# Power.net
KiCad netlist of a schematic drawn in Altium Designer
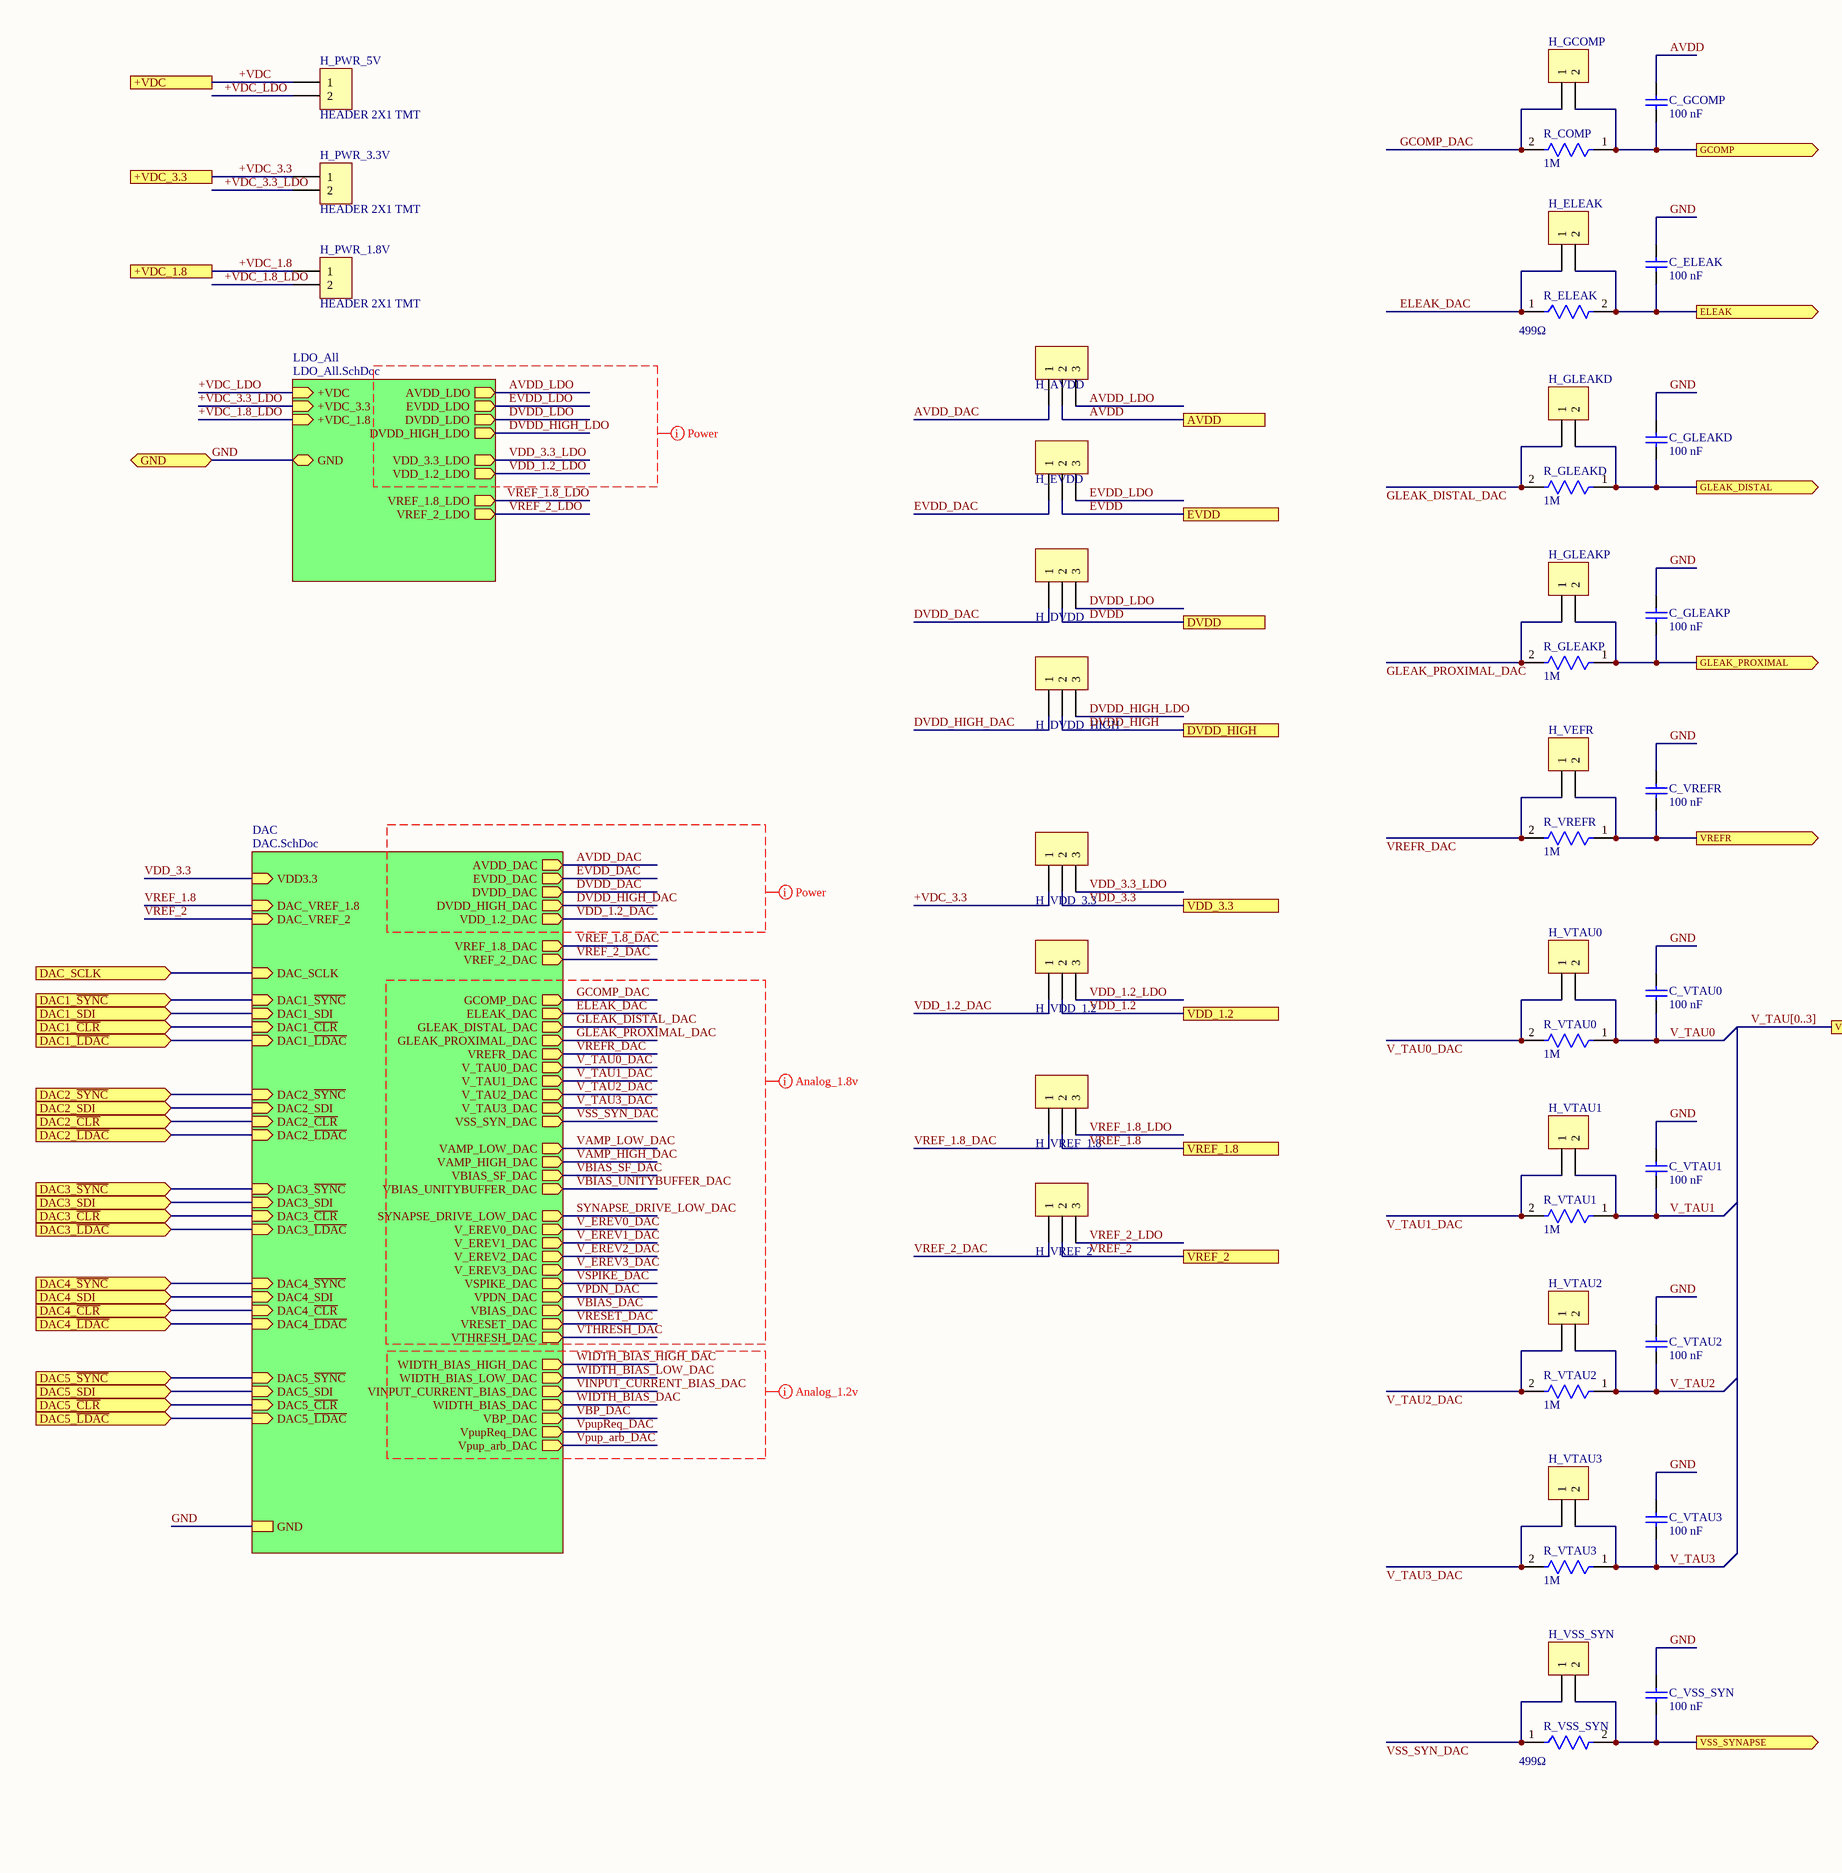
[diagram p0: Power.SchDoc, left]
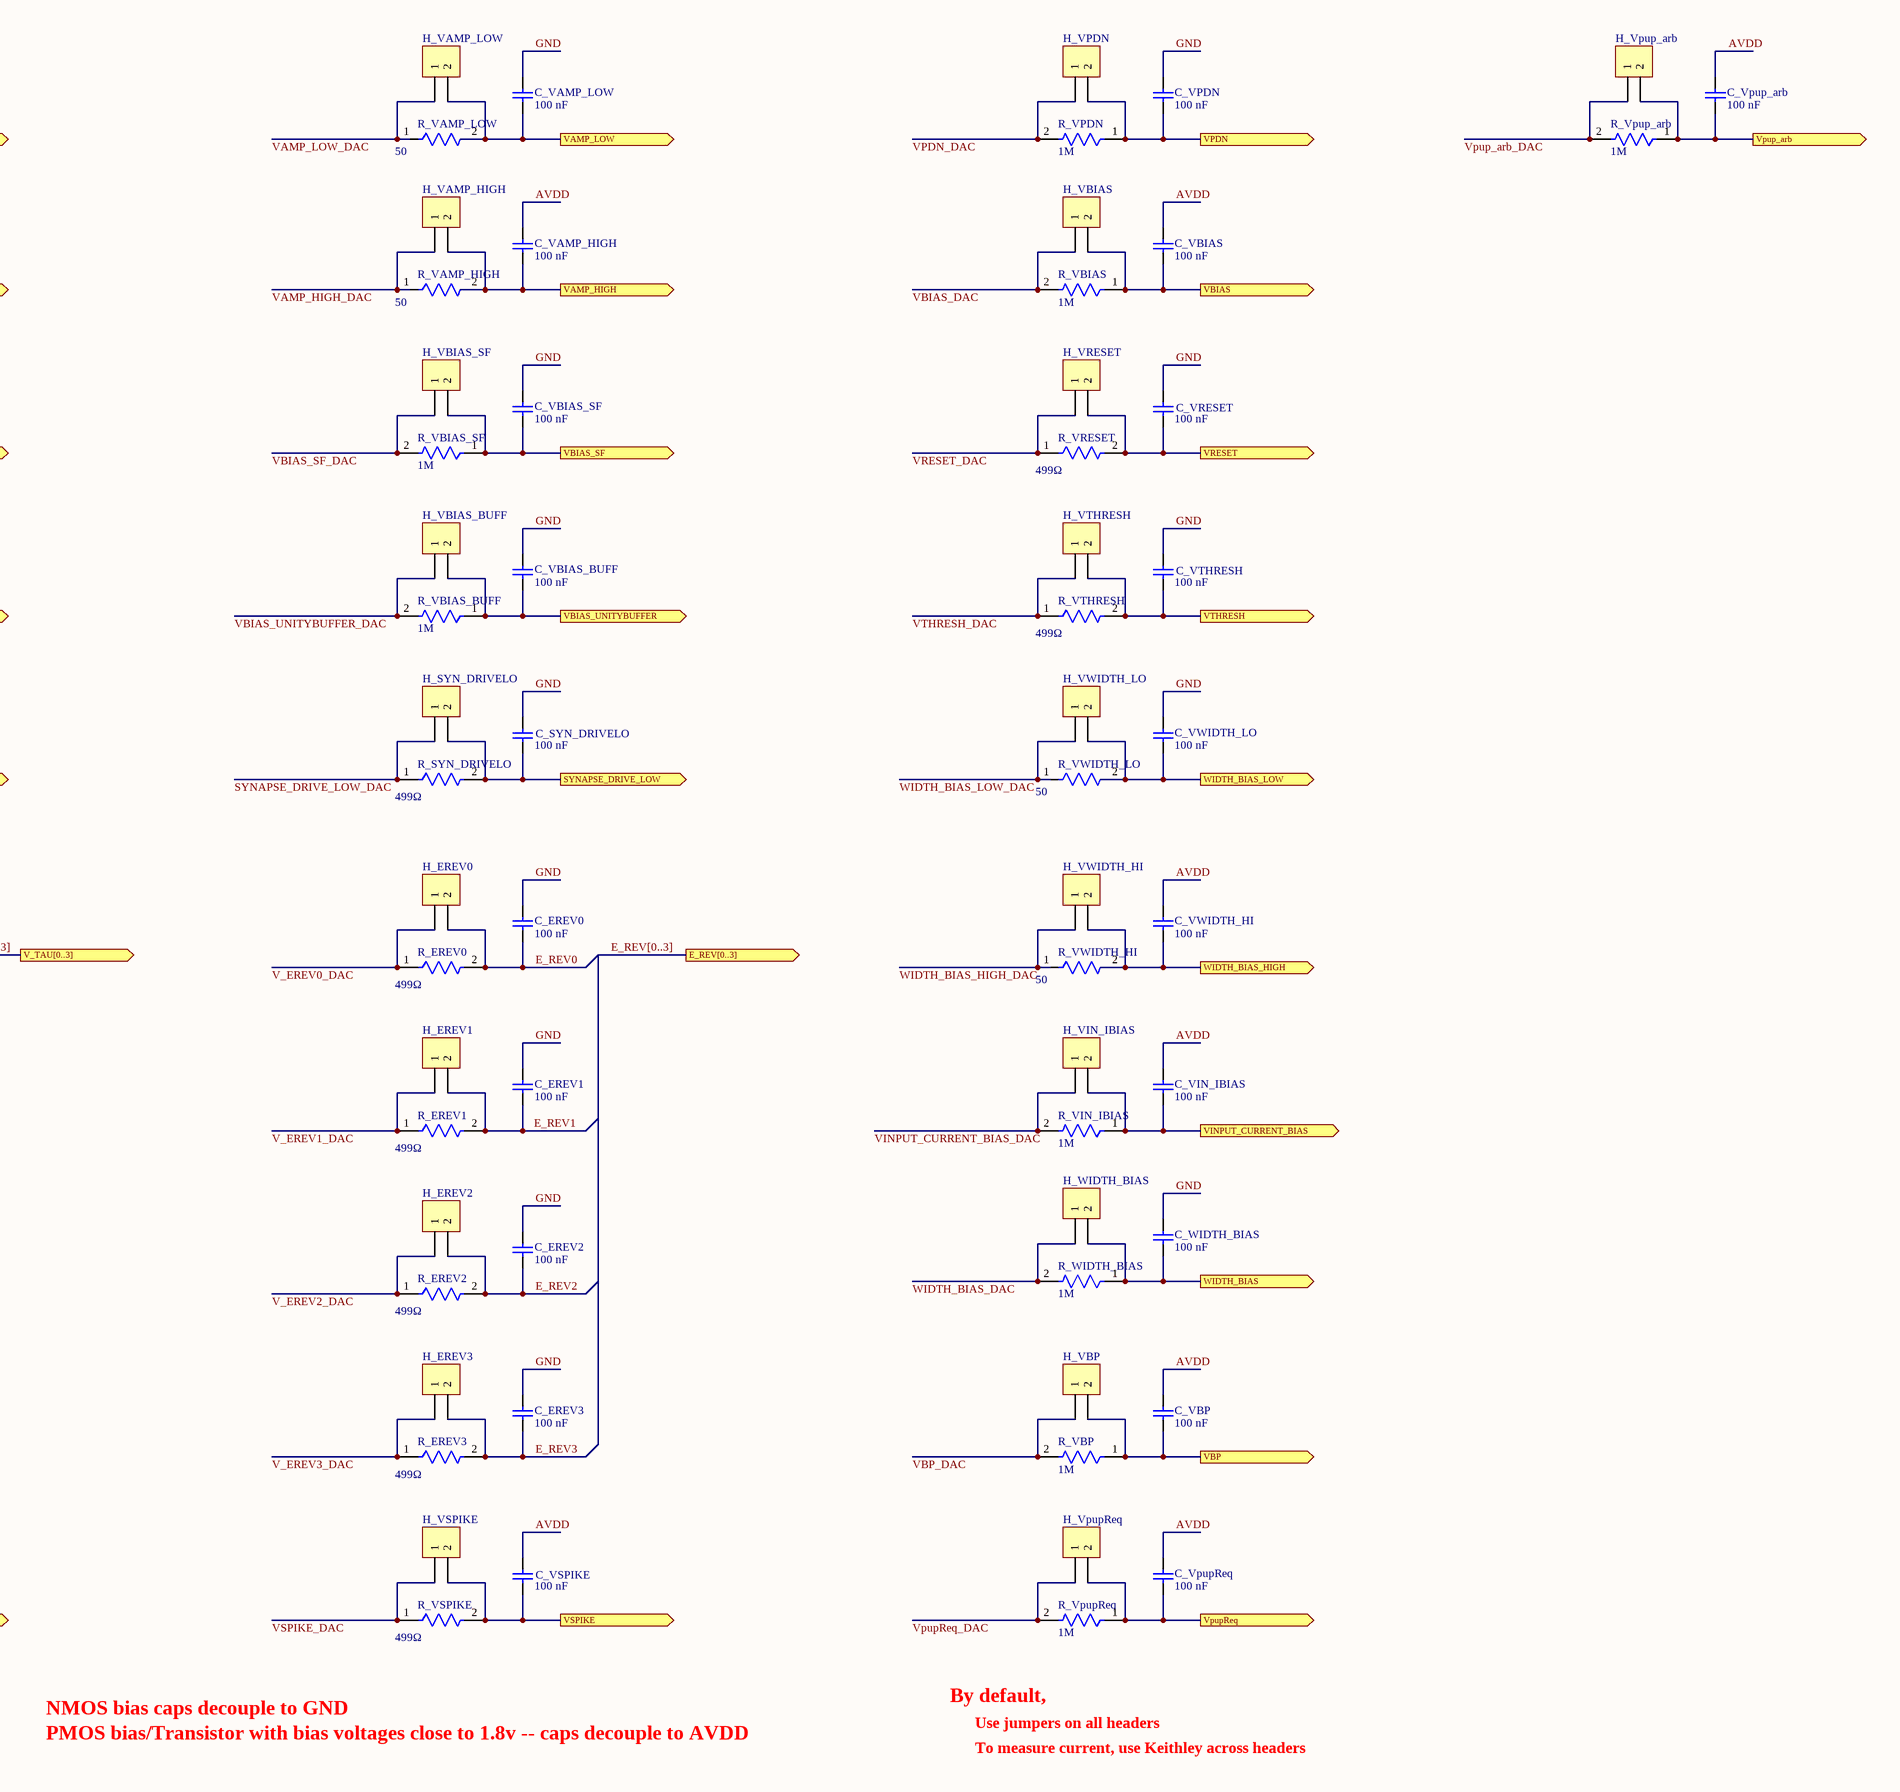
[diagram p1: Power.SchDoc, right]

(export (version "E")
  (design (tool "Eeschema 10.0.6"))
  (components
    (comp (ref "C_ELEAK")
      (value "100 nF")
      (footprint "KEMET C0805C104J8RACTU")
      (description "CAP CER 0.1UF 10V X7R 0805\r\n±10% 10V Ceramic Capacitor X7R 0805 (2012 Metric)")
      (fields (field (name "Comment") "Cap 100nF 0805"))
      (libsource (lib "MRI_ADC") (part "Cap 100nF 0805"))
    )
    (comp (ref "C_EREV0")
      (value "100 nF")
      (footprint "KEMET C0805C104J8RACTU")
      (description "CAP CER 0.1UF 10V X7R 0805\r\n±10% 10V Ceramic Capacitor X7R 0805 (2012 Metric)")
      (fields (field (name "Comment") "Cap 100nF 0805"))
      (libsource (lib "MRI_ADC") (part "Cap 100nF 0805"))
    )
    (comp (ref "C_EREV1")
      (value "100 nF")
      (footprint "KEMET C0805C104J8RACTU")
      (description "CAP CER 0.1UF 10V X7R 0805\r\n±10% 10V Ceramic Capacitor X7R 0805 (2012 Metric)")
      (fields (field (name "Comment") "Cap 100nF 0805"))
      (libsource (lib "MRI_ADC") (part "Cap 100nF 0805"))
    )
    (comp (ref "C_EREV2")
      (value "100 nF")
      (footprint "KEMET C0805C104J8RACTU")
      (description "CAP CER 0.1UF 10V X7R 0805\r\n±10% 10V Ceramic Capacitor X7R 0805 (2012 Metric)")
      (fields (field (name "Comment") "Cap 100nF 0805"))
      (libsource (lib "MRI_ADC") (part "Cap 100nF 0805"))
    )
    (comp (ref "C_EREV3")
      (value "100 nF")
      (footprint "KEMET C0805C104J8RACTU")
      (description "CAP CER 0.1UF 10V X7R 0805\r\n±10% 10V Ceramic Capacitor X7R 0805 (2012 Metric)")
      (fields (field (name "Comment") "Cap 100nF 0805"))
      (libsource (lib "MRI_ADC") (part "Cap 100nF 0805"))
    )
    (comp (ref "C_GCOMP")
      (value "100 nF")
      (footprint "KEMET C0805C104J8RACTU")
      (description "CAP CER 0.1UF 10V X7R 0805\r\n±10% 10V Ceramic Capacitor X7R 0805 (2012 Metric)")
      (fields (field (name "Comment") "Cap 100nF 0805"))
      (libsource (lib "MRI_ADC") (part "Cap 100nF 0805"))
    )
    (comp (ref "C_GLEAKD")
      (value "100 nF")
      (footprint "KEMET C0805C104J8RACTU")
      (description "CAP CER 0.1UF 10V X7R 0805\r\n±10% 10V Ceramic Capacitor X7R 0805 (2012 Metric)")
      (fields (field (name "Comment") "Cap 100nF 0805"))
      (libsource (lib "MRI_ADC") (part "Cap 100nF 0805"))
    )
    (comp (ref "C_GLEAKP")
      (value "100 nF")
      (footprint "KEMET C0805C104J8RACTU")
      (description "CAP CER 0.1UF 10V X7R 0805\r\n±10% 10V Ceramic Capacitor X7R 0805 (2012 Metric)")
      (fields (field (name "Comment") "Cap 100nF 0805"))
      (libsource (lib "MRI_ADC") (part "Cap 100nF 0805"))
    )
    (comp (ref "C_SYN_DRIVELO")
      (value "100 nF")
      (footprint "KEMET C0805C104J8RACTU")
      (description "CAP CER 0.1UF 10V X7R 0805\r\n±10% 10V Ceramic Capacitor X7R 0805 (2012 Metric)")
      (fields (field (name "Comment") "Cap 100nF 0805"))
      (libsource (lib "MRI_ADC") (part "Cap 100nF 0805"))
    )
    (comp (ref "C_VAMP_HIGH")
      (value "100 nF")
      (footprint "KEMET C0805C104J8RACTU")
      (description "CAP CER 0.1UF 10V X7R 0805\r\n±10% 10V Ceramic Capacitor X7R 0805 (2012 Metric)")
      (fields (field (name "Comment") "Cap 100nF 0805"))
      (libsource (lib "MRI_ADC") (part "Cap 100nF 0805"))
    )
    (comp (ref "C_VAMP_LOW")
      (value "100 nF")
      (footprint "KEMET C0805C104J8RACTU")
      (description "CAP CER 0.1UF 10V X7R 0805\r\n±10% 10V Ceramic Capacitor X7R 0805 (2012 Metric)")
      (fields (field (name "Comment") "Cap 100nF 0805"))
      (libsource (lib "MRI_ADC") (part "Cap 100nF 0805"))
    )
    (comp (ref "C_VBIAS")
      (value "100 nF")
      (footprint "KEMET C0805C104J8RACTU")
      (description "CAP CER 0.1UF 10V X7R 0805\r\n±10% 10V Ceramic Capacitor X7R 0805 (2012 Metric)")
      (fields (field (name "Comment") "Cap 100nF 0805"))
      (libsource (lib "MRI_ADC") (part "Cap 100nF 0805"))
    )
    (comp (ref "C_VBIAS_BUFF")
      (value "100 nF")
      (footprint "KEMET C0805C104J8RACTU")
      (description "CAP CER 0.1UF 10V X7R 0805\r\n±10% 10V Ceramic Capacitor X7R 0805 (2012 Metric)")
      (fields (field (name "Comment") "Cap 100nF 0805"))
      (libsource (lib "MRI_ADC") (part "Cap 100nF 0805"))
    )
    (comp (ref "C_VBIAS_SF")
      (value "100 nF")
      (footprint "KEMET C0805C104J8RACTU")
      (description "CAP CER 0.1UF 10V X7R 0805\r\n±10% 10V Ceramic Capacitor X7R 0805 (2012 Metric)")
      (fields (field (name "Comment") "Cap 100nF 0805"))
      (libsource (lib "MRI_ADC") (part "Cap 100nF 0805"))
    )
    (comp (ref "C_VBP")
      (value "100 nF")
      (footprint "KEMET C0805C104J8RACTU")
      (description "CAP CER 0.1UF 10V X7R 0805\r\n±10% 10V Ceramic Capacitor X7R 0805 (2012 Metric)")
      (fields (field (name "Comment") "Cap 100nF 0805"))
      (libsource (lib "MRI_ADC") (part "Cap 100nF 0805"))
    )
    (comp (ref "C_VIN_IBIAS")
      (value "100 nF")
      (footprint "KEMET C0805C104J8RACTU")
      (description "CAP CER 0.1UF 10V X7R 0805\r\n±10% 10V Ceramic Capacitor X7R 0805 (2012 Metric)")
      (fields (field (name "Comment") "Cap 100nF 0805"))
      (libsource (lib "MRI_ADC") (part "Cap 100nF 0805"))
    )
    (comp (ref "C_VPDN")
      (value "100 nF")
      (footprint "KEMET C0805C104J8RACTU")
      (description "CAP CER 0.1UF 10V X7R 0805\r\n±10% 10V Ceramic Capacitor X7R 0805 (2012 Metric)")
      (fields (field (name "Comment") "Cap 100nF 0805"))
      (libsource (lib "MRI_ADC") (part "Cap 100nF 0805"))
    )
    (comp (ref "C_VpupReq")
      (value "100 nF")
      (footprint "KEMET C0805C104J8RACTU")
      (description "CAP CER 0.1UF 10V X7R 0805\r\n±10% 10V Ceramic Capacitor X7R 0805 (2012 Metric)")
      (fields (field (name "Comment") "Cap 100nF 0805"))
      (libsource (lib "MRI_ADC") (part "Cap 100nF 0805"))
    )
    (comp (ref "C_Vpup_arb")
      (value "100 nF")
      (footprint "KEMET C0805C104J8RACTU")
      (description "CAP CER 0.1UF 10V X7R 0805\r\n±10% 10V Ceramic Capacitor X7R 0805 (2012 Metric)")
      (fields (field (name "Comment") "Cap 100nF 0805"))
      (libsource (lib "MRI_ADC") (part "Cap 100nF 0805"))
    )
    (comp (ref "C_VREFR")
      (value "100 nF")
      (footprint "KEMET C0805C104J8RACTU")
      (description "CAP CER 0.1UF 10V X7R 0805\r\n±10% 10V Ceramic Capacitor X7R 0805 (2012 Metric)")
      (fields (field (name "Comment") "Cap 100nF 0805"))
      (libsource (lib "MRI_ADC") (part "Cap 100nF 0805"))
    )
    (comp (ref "C_VRESET")
      (value "100 nF")
      (footprint "KEMET C0805C104J8RACTU")
      (description "CAP CER 0.1UF 10V X7R 0805\r\n±10% 10V Ceramic Capacitor X7R 0805 (2012 Metric)")
      (fields (field (name "Comment") "Cap 100nF 0805"))
      (libsource (lib "MRI_ADC") (part "Cap 100nF 0805"))
    )
    (comp (ref "C_VSPIKE")
      (value "100 nF")
      (footprint "KEMET C0805C104J8RACTU")
      (description "CAP CER 0.1UF 10V X7R 0805\r\n±10% 10V Ceramic Capacitor X7R 0805 (2012 Metric)")
      (fields (field (name "Comment") "Cap 100nF 0805"))
      (libsource (lib "MRI_ADC") (part "Cap 100nF 0805"))
    )
    (comp (ref "C_VSS_SYN")
      (value "100 nF")
      (footprint "KEMET C0805C104J8RACTU")
      (description "CAP CER 0.1UF 10V X7R 0805\r\n±10% 10V Ceramic Capacitor X7R 0805 (2012 Metric)")
      (fields (field (name "Comment") "Cap 100nF 0805"))
      (libsource (lib "MRI_ADC") (part "Cap 100nF 0805"))
    )
    (comp (ref "C_VTAU0")
      (value "100 nF")
      (footprint "KEMET C0805C104J8RACTU")
      (description "CAP CER 0.1UF 10V X7R 0805\r\n±10% 10V Ceramic Capacitor X7R 0805 (2012 Metric)")
      (fields (field (name "Comment") "Cap 100nF 0805"))
      (libsource (lib "MRI_ADC") (part "Cap 100nF 0805"))
    )
    (comp (ref "C_VTAU1")
      (value "100 nF")
      (footprint "KEMET C0805C104J8RACTU")
      (description "CAP CER 0.1UF 10V X7R 0805\r\n±10% 10V Ceramic Capacitor X7R 0805 (2012 Metric)")
      (fields (field (name "Comment") "Cap 100nF 0805"))
      (libsource (lib "MRI_ADC") (part "Cap 100nF 0805"))
    )
    (comp (ref "C_VTAU2")
      (value "100 nF")
      (footprint "KEMET C0805C104J8RACTU")
      (description "CAP CER 0.1UF 10V X7R 0805\r\n±10% 10V Ceramic Capacitor X7R 0805 (2012 Metric)")
      (fields (field (name "Comment") "Cap 100nF 0805"))
      (libsource (lib "MRI_ADC") (part "Cap 100nF 0805"))
    )
    (comp (ref "C_VTAU3")
      (value "100 nF")
      (footprint "KEMET C0805C104J8RACTU")
      (description "CAP CER 0.1UF 10V X7R 0805\r\n±10% 10V Ceramic Capacitor X7R 0805 (2012 Metric)")
      (fields (field (name "Comment") "Cap 100nF 0805"))
      (libsource (lib "MRI_ADC") (part "Cap 100nF 0805"))
    )
    (comp (ref "C_VTHRESH")
      (value "100 nF")
      (footprint "KEMET C0805C104J8RACTU")
      (description "CAP CER 0.1UF 10V X7R 0805\r\n±10% 10V Ceramic Capacitor X7R 0805 (2012 Metric)")
      (fields (field (name "Comment") "Cap 100nF 0805"))
      (libsource (lib "MRI_ADC") (part "Cap 100nF 0805"))
    )
    (comp (ref "C_VWIDTH_HI")
      (value "100 nF")
      (footprint "KEMET C0805C104J8RACTU")
      (description "CAP CER 0.1UF 10V X7R 0805\r\n±10% 10V Ceramic Capacitor X7R 0805 (2012 Metric)")
      (fields (field (name "Comment") "Cap 100nF 0805"))
      (libsource (lib "MRI_ADC") (part "Cap 100nF 0805"))
    )
    (comp (ref "C_VWIDTH_LO")
      (value "100 nF")
      (footprint "KEMET C0805C104J8RACTU")
      (description "CAP CER 0.1UF 10V X7R 0805\r\n±10% 10V Ceramic Capacitor X7R 0805 (2012 Metric)")
      (fields (field (name "Comment") "Cap 100nF 0805"))
      (libsource (lib "MRI_ADC") (part "Cap 100nF 0805"))
    )
    (comp (ref "C_WIDTH_BIAS")
      (value "100 nF")
      (footprint "KEMET C0805C104J8RACTU")
      (description "CAP CER 0.1UF 10V X7R 0805\r\n±10% 10V Ceramic Capacitor X7R 0805 (2012 Metric)")
      (fields (field (name "Comment") "Cap 100nF 0805"))
      (libsource (lib "MRI_ADC") (part "Cap 100nF 0805"))
    )
    (comp (ref "H_AVDD")
      (value "HEADER 3X1 TMT")
      (footprint "Samtec TSW-103-07-L-S")
      (description "CONN HEADER VERT 3POS 2.54MM\r\nConnector Header Through Hole 3 position 0.100\" (2.54mm)")
      (libsource (lib "MRI_ADC") (part "HEADER 3X1 TMT"))
    )
    (comp (ref "H_DVDD")
      (value "HEADER 3X1 TMT")
      (footprint "Samtec TSW-103-07-L-S")
      (description "CONN HEADER VERT 3POS 2.54MM\r\nConnector Header Through Hole 3 position 0.100\" (2.54mm)")
      (libsource (lib "MRI_ADC") (part "HEADER 3X1 TMT"))
    )
    (comp (ref "H_DVDD_HIGH")
      (value "HEADER 3X1 TMT")
      (footprint "Samtec TSW-103-07-L-S")
      (description "CONN HEADER VERT 3POS 2.54MM\r\nConnector Header Through Hole 3 position 0.100\" (2.54mm)")
      (libsource (lib "MRI_ADC") (part "HEADER 3X1 TMT"))
    )
    (comp (ref "H_ELEAK")
      (value "HEADER 2X1 TMT")
      (footprint "Samtec TSW-102-07-G-S")
      (description "CONN HEADER VERT 2POS 2.54MM\r\nConnector Header Through Hole 2 position 0.100\" (2.54mm)")
      (libsource (lib "MRI_ADC") (part "HEADER 2X1 TMT"))
    )
    (comp (ref "H_EREV0")
      (value "HEADER 2X1 TMT")
      (footprint "Samtec TSW-102-07-G-S")
      (description "CONN HEADER VERT 2POS 2.54MM\r\nConnector Header Through Hole 2 position 0.100\" (2.54mm)")
      (libsource (lib "MRI_ADC") (part "HEADER 2X1 TMT"))
    )
    (comp (ref "H_EREV1")
      (value "HEADER 2X1 TMT")
      (footprint "Samtec TSW-102-07-G-S")
      (description "CONN HEADER VERT 2POS 2.54MM\r\nConnector Header Through Hole 2 position 0.100\" (2.54mm)")
      (libsource (lib "MRI_ADC") (part "HEADER 2X1 TMT"))
    )
    (comp (ref "H_EREV2")
      (value "HEADER 2X1 TMT")
      (footprint "Samtec TSW-102-07-G-S")
      (description "CONN HEADER VERT 2POS 2.54MM\r\nConnector Header Through Hole 2 position 0.100\" (2.54mm)")
      (libsource (lib "MRI_ADC") (part "HEADER 2X1 TMT"))
    )
    (comp (ref "H_EREV3")
      (value "HEADER 2X1 TMT")
      (footprint "Samtec TSW-102-07-G-S")
      (description "CONN HEADER VERT 2POS 2.54MM\r\nConnector Header Through Hole 2 position 0.100\" (2.54mm)")
      (libsource (lib "MRI_ADC") (part "HEADER 2X1 TMT"))
    )
    (comp (ref "H_EVDD")
      (value "HEADER 3X1 TMT")
      (footprint "Samtec TSW-103-07-L-S")
      (description "CONN HEADER VERT 3POS 2.54MM\r\nConnector Header Through Hole 3 position 0.100\" (2.54mm)")
      (libsource (lib "MRI_ADC") (part "HEADER 3X1 TMT"))
    )
    (comp (ref "H_GCOMP")
      (value "HEADER 2X1 TMT")
      (footprint "Samtec TSW-102-07-G-S")
      (description "CONN HEADER VERT 2POS 2.54MM\r\nConnector Header Through Hole 2 position 0.100\" (2.54mm)")
      (libsource (lib "MRI_ADC") (part "HEADER 2X1 TMT"))
    )
    (comp (ref "H_GLEAKD")
      (value "HEADER 2X1 TMT")
      (footprint "Samtec TSW-102-07-G-S")
      (description "CONN HEADER VERT 2POS 2.54MM\r\nConnector Header Through Hole 2 position 0.100\" (2.54mm)")
      (libsource (lib "MRI_ADC") (part "HEADER 2X1 TMT"))
    )
    (comp (ref "H_GLEAKP")
      (value "HEADER 2X1 TMT")
      (footprint "Samtec TSW-102-07-G-S")
      (description "CONN HEADER VERT 2POS 2.54MM\r\nConnector Header Through Hole 2 position 0.100\" (2.54mm)")
      (libsource (lib "MRI_ADC") (part "HEADER 2X1 TMT"))
    )
    (comp (ref "H_PWR_1.8V")
      (value "HEADER 2X1 TMT")
      (footprint "Samtec TSW-102-07-G-S")
      (description "CONN HEADER VERT 2POS 2.54MM\r\nConnector Header Through Hole 2 position 0.100\" (2.54mm)")
      (libsource (lib "") (part "HEADER 2X1 TMT_1"))
    )
    (comp (ref "H_PWR_3.3V")
      (value "HEADER 2X1 TMT")
      (footprint "Samtec TSW-102-07-G-S")
      (description "CONN HEADER VERT 2POS 2.54MM\r\nConnector Header Through Hole 2 position 0.100\" (2.54mm)")
      (libsource (lib "") (part "HEADER 2X1 TMT_1"))
    )
    (comp (ref "H_PWR_5V")
      (value "HEADER 2X1 TMT")
      (footprint "Samtec TSW-102-07-G-S")
      (description "CONN HEADER VERT 2POS 2.54MM\r\nConnector Header Through Hole 2 position 0.100\" (2.54mm)")
      (libsource (lib "") (part "HEADER 2X1 TMT_1"))
    )
    (comp (ref "H_SYN_DRIVELO")
      (value "HEADER 2X1 TMT")
      (footprint "Samtec TSW-102-07-G-S")
      (description "CONN HEADER VERT 2POS 2.54MM\r\nConnector Header Through Hole 2 position 0.100\" (2.54mm)")
      (libsource (lib "MRI_ADC") (part "HEADER 2X1 TMT"))
    )
    (comp (ref "H_VAMP_HIGH")
      (value "HEADER 2X1 TMT")
      (footprint "Samtec TSW-102-07-G-S")
      (description "CONN HEADER VERT 2POS 2.54MM\r\nConnector Header Through Hole 2 position 0.100\" (2.54mm)")
      (libsource (lib "MRI_ADC") (part "HEADER 2X1 TMT"))
    )
    (comp (ref "H_VAMP_LOW")
      (value "HEADER 2X1 TMT")
      (footprint "Samtec TSW-102-07-G-S")
      (description "CONN HEADER VERT 2POS 2.54MM\r\nConnector Header Through Hole 2 position 0.100\" (2.54mm)")
      (libsource (lib "MRI_ADC") (part "HEADER 2X1 TMT"))
    )
    (comp (ref "H_VBIAS")
      (value "HEADER 2X1 TMT")
      (footprint "Samtec TSW-102-07-G-S")
      (description "CONN HEADER VERT 2POS 2.54MM\r\nConnector Header Through Hole 2 position 0.100\" (2.54mm)")
      (libsource (lib "MRI_ADC") (part "HEADER 2X1 TMT"))
    )
    (comp (ref "H_VBIAS_BUFF")
      (value "HEADER 2X1 TMT")
      (footprint "Samtec TSW-102-07-G-S")
      (description "CONN HEADER VERT 2POS 2.54MM\r\nConnector Header Through Hole 2 position 0.100\" (2.54mm)")
      (libsource (lib "MRI_ADC") (part "HEADER 2X1 TMT"))
    )
    (comp (ref "H_VBIAS_SF")
      (value "HEADER 2X1 TMT")
      (footprint "Samtec TSW-102-07-G-S")
      (description "CONN HEADER VERT 2POS 2.54MM\r\nConnector Header Through Hole 2 position 0.100\" (2.54mm)")
      (libsource (lib "MRI_ADC") (part "HEADER 2X1 TMT"))
    )
    (comp (ref "H_VBP")
      (value "HEADER 2X1 TMT")
      (footprint "Samtec TSW-102-07-G-S")
      (description "CONN HEADER VERT 2POS 2.54MM\r\nConnector Header Through Hole 2 position 0.100\" (2.54mm)")
      (libsource (lib "MRI_ADC") (part "HEADER 2X1 TMT"))
    )
    (comp (ref "H_VDD_1.2")
      (value "HEADER 3X1 TMT")
      (footprint "Samtec TSW-103-07-L-S")
      (description "CONN HEADER VERT 3POS 2.54MM\r\nConnector Header Through Hole 3 position 0.100\" (2.54mm)")
      (libsource (lib "MRI_ADC") (part "HEADER 3X1 TMT"))
    )
    (comp (ref "H_VDD_3.3")
      (value "HEADER 3X1 TMT")
      (footprint "Samtec TSW-103-07-L-S")
      (description "CONN HEADER VERT 3POS 2.54MM\r\nConnector Header Through Hole 3 position 0.100\" (2.54mm)")
      (libsource (lib "MRI_ADC") (part "HEADER 3X1 TMT"))
    )
    (comp (ref "H_VEFR")
      (value "HEADER 2X1 TMT")
      (footprint "Samtec TSW-102-07-G-S")
      (description "CONN HEADER VERT 2POS 2.54MM\r\nConnector Header Through Hole 2 position 0.100\" (2.54mm)")
      (libsource (lib "MRI_ADC") (part "HEADER 2X1 TMT"))
    )
    (comp (ref "H_VIN_IBIAS")
      (value "HEADER 2X1 TMT")
      (footprint "Samtec TSW-102-07-G-S")
      (description "CONN HEADER VERT 2POS 2.54MM\r\nConnector Header Through Hole 2 position 0.100\" (2.54mm)")
      (libsource (lib "MRI_ADC") (part "HEADER 2X1 TMT"))
    )
    (comp (ref "H_VPDN")
      (value "HEADER 2X1 TMT")
      (footprint "Samtec TSW-102-07-G-S")
      (description "CONN HEADER VERT 2POS 2.54MM\r\nConnector Header Through Hole 2 position 0.100\" (2.54mm)")
      (libsource (lib "MRI_ADC") (part "HEADER 2X1 TMT"))
    )
    (comp (ref "H_VpupReq")
      (value "HEADER 2X1 TMT")
      (footprint "Samtec TSW-102-07-G-S")
      (description "CONN HEADER VERT 2POS 2.54MM\r\nConnector Header Through Hole 2 position 0.100\" (2.54mm)")
      (libsource (lib "MRI_ADC") (part "HEADER 2X1 TMT"))
    )
    (comp (ref "H_Vpup_arb")
      (value "HEADER 2X1 TMT")
      (footprint "Samtec TSW-102-07-G-S")
      (description "CONN HEADER VERT 2POS 2.54MM\r\nConnector Header Through Hole 2 position 0.100\" (2.54mm)")
      (libsource (lib "MRI_ADC") (part "HEADER 2X1 TMT"))
    )
    (comp (ref "H_VREF_1.8")
      (value "HEADER 3X1 TMT")
      (footprint "Samtec TSW-103-07-L-S")
      (description "CONN HEADER VERT 3POS 2.54MM\r\nConnector Header Through Hole 3 position 0.100\" (2.54mm)")
      (libsource (lib "MRI_ADC") (part "HEADER 3X1 TMT"))
    )
    (comp (ref "H_VREF_2")
      (value "HEADER 3X1 TMT")
      (footprint "Samtec TSW-103-07-L-S")
      (description "CONN HEADER VERT 3POS 2.54MM\r\nConnector Header Through Hole 3 position 0.100\" (2.54mm)")
      (libsource (lib "MRI_ADC") (part "HEADER 3X1 TMT"))
    )
    (comp (ref "H_VRESET")
      (value "HEADER 2X1 TMT")
      (footprint "Samtec TSW-102-07-G-S")
      (description "CONN HEADER VERT 2POS 2.54MM\r\nConnector Header Through Hole 2 position 0.100\" (2.54mm)")
      (libsource (lib "MRI_ADC") (part "HEADER 2X1 TMT"))
    )
    (comp (ref "H_VSPIKE")
      (value "HEADER 2X1 TMT")
      (footprint "Samtec TSW-102-07-G-S")
      (description "CONN HEADER VERT 2POS 2.54MM\r\nConnector Header Through Hole 2 position 0.100\" (2.54mm)")
      (libsource (lib "MRI_ADC") (part "HEADER 2X1 TMT"))
    )
    (comp (ref "H_VSS_SYN")
      (value "HEADER 2X1 TMT")
      (footprint "Samtec TSW-102-07-G-S")
      (description "CONN HEADER VERT 2POS 2.54MM\r\nConnector Header Through Hole 2 position 0.100\" (2.54mm)")
      (libsource (lib "MRI_ADC") (part "HEADER 2X1 TMT"))
    )
    (comp (ref "H_VTAU0")
      (value "HEADER 2X1 TMT")
      (footprint "Samtec TSW-102-07-G-S")
      (description "CONN HEADER VERT 2POS 2.54MM\r\nConnector Header Through Hole 2 position 0.100\" (2.54mm)")
      (libsource (lib "MRI_ADC") (part "HEADER 2X1 TMT"))
    )
    (comp (ref "H_VTAU1")
      (value "HEADER 2X1 TMT")
      (footprint "Samtec TSW-102-07-G-S")
      (description "CONN HEADER VERT 2POS 2.54MM\r\nConnector Header Through Hole 2 position 0.100\" (2.54mm)")
      (libsource (lib "MRI_ADC") (part "HEADER 2X1 TMT"))
    )
    (comp (ref "H_VTAU2")
      (value "HEADER 2X1 TMT")
      (footprint "Samtec TSW-102-07-G-S")
      (description "CONN HEADER VERT 2POS 2.54MM\r\nConnector Header Through Hole 2 position 0.100\" (2.54mm)")
      (libsource (lib "MRI_ADC") (part "HEADER 2X1 TMT"))
    )
    (comp (ref "H_VTAU3")
      (value "HEADER 2X1 TMT")
      (footprint "Samtec TSW-102-07-G-S")
      (description "CONN HEADER VERT 2POS 2.54MM\r\nConnector Header Through Hole 2 position 0.100\" (2.54mm)")
      (libsource (lib "MRI_ADC") (part "HEADER 2X1 TMT"))
    )
    (comp (ref "H_VTHRESH")
      (value "HEADER 2X1 TMT")
      (footprint "Samtec TSW-102-07-G-S")
      (description "CONN HEADER VERT 2POS 2.54MM\r\nConnector Header Through Hole 2 position 0.100\" (2.54mm)")
      (libsource (lib "MRI_ADC") (part "HEADER 2X1 TMT"))
    )
    (comp (ref "H_VWIDTH_HI")
      (value "HEADER 2X1 TMT")
      (footprint "Samtec TSW-102-07-G-S")
      (description "CONN HEADER VERT 2POS 2.54MM\r\nConnector Header Through Hole 2 position 0.100\" (2.54mm)")
      (libsource (lib "MRI_ADC") (part "HEADER 2X1 TMT"))
    )
    (comp (ref "H_VWIDTH_LO")
      (value "HEADER 2X1 TMT")
      (footprint "Samtec TSW-102-07-G-S")
      (description "CONN HEADER VERT 2POS 2.54MM\r\nConnector Header Through Hole 2 position 0.100\" (2.54mm)")
      (libsource (lib "MRI_ADC") (part "HEADER 2X1 TMT"))
    )
    (comp (ref "H_WIDTH_BIAS")
      (value "HEADER 2X1 TMT")
      (footprint "Samtec TSW-102-07-G-S")
      (description "CONN HEADER VERT 2POS 2.54MM\r\nConnector Header Through Hole 2 position 0.100\" (2.54mm)")
      (libsource (lib "MRI_ADC") (part "HEADER 2X1 TMT"))
    )
    (comp (ref "R_COMP")
      (value "1M")
      (footprint "FP-CRCW0603-e3-MFG")
      (description "RES Thick Film, 1MΩ, 1%, 0.1W, 100ppm/°C, 0603")
      (fields (field (name "TOLERANCE") "1%"))
      (libsource (lib "Altium Content Vault") (part "1029c3af85768c4190bb7ad29bc67b5"))
    )
    (comp (ref "R_ELEAK")
      (value "RP73PF1J499RBTDF")
      (footprint "FP-RP73P-1J-MFG")
      (description "RP73P 0603 499Ω 0.166W 25ppm/°C 0.10% 100V")
      (fields (field (name "RESISTANCE") "499Ω") (field (name "TOLERANCE") "0.001"))
      (libsource (lib "Altium Content Vault") (part "1029c3af85768c4190bb7ad29bc67b5"))
    )
    (comp (ref "R_EREV0")
      (value "RP73PF1J499RBTDF")
      (footprint "FP-RP73P-1J-MFG")
      (description "RP73P 0603 499Ω 0.166W 25ppm/°C 0.10% 100V")
      (fields (field (name "RESISTANCE") "499Ω") (field (name "TOLERANCE") "0.001"))
      (libsource (lib "Altium Content Vault") (part "1029c3af85768c4190bb7ad29bc67b5"))
    )
    (comp (ref "R_EREV1")
      (value "RP73PF1J499RBTDF")
      (footprint "FP-RP73P-1J-MFG")
      (description "RP73P 0603 499Ω 0.166W 25ppm/°C 0.10% 100V")
      (fields (field (name "RESISTANCE") "499Ω") (field (name "TOLERANCE") "0.001"))
      (libsource (lib "Altium Content Vault") (part "1029c3af85768c4190bb7ad29bc67b5"))
    )
    (comp (ref "R_EREV2")
      (value "RP73PF1J499RBTDF")
      (footprint "FP-RP73P-1J-MFG")
      (description "RP73P 0603 499Ω 0.166W 25ppm/°C 0.10% 100V")
      (fields (field (name "RESISTANCE") "499Ω") (field (name "TOLERANCE") "0.001"))
      (libsource (lib "Altium Content Vault") (part "1029c3af85768c4190bb7ad29bc67b5"))
    )
    (comp (ref "R_EREV3")
      (value "RP73PF1J499RBTDF")
      (footprint "FP-RP73P-1J-MFG")
      (description "RP73P 0603 499Ω 0.166W 25ppm/°C 0.10% 100V")
      (fields (field (name "RESISTANCE") "499Ω") (field (name "TOLERANCE") "0.001"))
      (libsource (lib "Altium Content Vault") (part "1029c3af85768c4190bb7ad29bc67b5"))
    )
    (comp (ref "R_GLEAKD")
      (value "1M")
      (footprint "FP-CRCW0603-e3-MFG")
      (description "RES Thick Film, 1MΩ, 1%, 0.1W, 100ppm/°C, 0603")
      (fields (field (name "TOLERANCE") "1%"))
      (libsource (lib "Altium Content Vault") (part "1029c3af85768c4190bb7ad29bc67b5"))
    )
    (comp (ref "R_GLEAKP")
      (value "1M")
      (footprint "FP-CRCW0603-e3-MFG")
      (description "RES Thick Film, 1MΩ, 1%, 0.1W, 100ppm/°C, 0603")
      (fields (field (name "TOLERANCE") "1%"))
      (libsource (lib "Altium Content Vault") (part "1029c3af85768c4190bb7ad29bc67b5"))
    )
    (comp (ref "R_SYN_DRIVELO")
      (value "RP73PF1J499RBTDF")
      (footprint "FP-RP73P-1J-MFG")
      (description "RP73P 0603 499Ω 0.166W 25ppm/°C 0.10% 100V")
      (fields (field (name "RESISTANCE") "499Ω") (field (name "TOLERANCE") "0.001"))
      (libsource (lib "Altium Content Vault") (part "1029c3af85768c4190bb7ad29bc67b5"))
    )
    (comp (ref "R_VAMP_HIGH")
      (value "RN731ETTP50R0F50")
      (footprint "FP-RN731E-IPC_A")
      (description "50Ω ±1% 0.063W, 1/16W Chip Resistor 0402 (1005 Metric) Moisture Resistant Thin Film")
      (fields (field (name "RESISTANCE") "50"))
      (libsource (lib "Altium Content Vault") (part "1029c3af85768c4190bb7ad29bc67b5"))
    )
    (comp (ref "R_VAMP_LOW")
      (value "RN731ETTP50R0F50")
      (footprint "FP-RN731E-IPC_A")
      (description "50Ω ±1% 0.063W, 1/16W Chip Resistor 0402 (1005 Metric) Moisture Resistant Thin Film")
      (fields (field (name "RESISTANCE") "50"))
      (libsource (lib "Altium Content Vault") (part "1029c3af85768c4190bb7ad29bc67b5"))
    )
    (comp (ref "R_VBIAS")
      (value "1M")
      (footprint "FP-CRCW0603-e3-MFG")
      (description "RES Thick Film, 1MΩ, 1%, 0.1W, 100ppm/°C, 0603")
      (fields (field (name "TOLERANCE") "1%"))
      (libsource (lib "Altium Content Vault") (part "1029c3af85768c4190bb7ad29bc67b5"))
    )
    (comp (ref "R_VBIAS_BUFF")
      (value "1M")
      (footprint "FP-CRCW0603-e3-MFG")
      (description "RES Thick Film, 1MΩ, 1%, 0.1W, 100ppm/°C, 0603")
      (fields (field (name "TOLERANCE") "1%"))
      (libsource (lib "Altium Content Vault") (part "1029c3af85768c4190bb7ad29bc67b5"))
    )
    (comp (ref "R_VBIAS_SF")
      (value "1M")
      (footprint "FP-CRCW0603-e3-MFG")
      (description "RES Thick Film, 1MΩ, 1%, 0.1W, 100ppm/°C, 0603")
      (fields (field (name "TOLERANCE") "1%"))
      (libsource (lib "Altium Content Vault") (part "1029c3af85768c4190bb7ad29bc67b5"))
    )
    (comp (ref "R_VBP")
      (value "1M")
      (footprint "FP-CRCW0603-e3-MFG")
      (description "RES Thick Film, 1MΩ, 1%, 0.1W, 100ppm/°C, 0603")
      (fields (field (name "TOLERANCE") "1%"))
      (libsource (lib "Altium Content Vault") (part "1029c3af85768c4190bb7ad29bc67b5"))
    )
    (comp (ref "R_VIN_IBIAS")
      (value "1M")
      (footprint "FP-CRCW0603-e3-MFG")
      (description "RES Thick Film, 1MΩ, 1%, 0.1W, 100ppm/°C, 0603")
      (fields (field (name "TOLERANCE") "1%"))
      (libsource (lib "Altium Content Vault") (part "1029c3af85768c4190bb7ad29bc67b5"))
    )
    (comp (ref "R_VPDN")
      (value "1M")
      (footprint "FP-CRCW0603-e3-MFG")
      (description "RES Thick Film, 1MΩ, 1%, 0.1W, 100ppm/°C, 0603")
      (fields (field (name "TOLERANCE") "1%"))
      (libsource (lib "Altium Content Vault") (part "1029c3af85768c4190bb7ad29bc67b5"))
    )
    (comp (ref "R_VpupReq")
      (value "1M")
      (footprint "FP-CRCW0603-e3-MFG")
      (description "RES Thick Film, 1MΩ, 1%, 0.1W, 100ppm/°C, 0603")
      (fields (field (name "TOLERANCE") "1%"))
      (libsource (lib "Altium Content Vault") (part "1029c3af85768c4190bb7ad29bc67b5"))
    )
    (comp (ref "R_Vpup_arb")
      (value "1M")
      (footprint "FP-CRCW0603-e3-MFG")
      (description "RES Thick Film, 1MΩ, 1%, 0.1W, 100ppm/°C, 0603")
      (fields (field (name "TOLERANCE") "1%"))
      (libsource (lib "Altium Content Vault") (part "1029c3af85768c4190bb7ad29bc67b5"))
    )
    (comp (ref "R_VREFR")
      (value "1M")
      (footprint "FP-CRCW0603-e3-MFG")
      (description "RES Thick Film, 1MΩ, 1%, 0.1W, 100ppm/°C, 0603")
      (fields (field (name "TOLERANCE") "1%"))
      (libsource (lib "Altium Content Vault") (part "1029c3af85768c4190bb7ad29bc67b5"))
    )
    (comp (ref "R_VRESET")
      (value "RP73PF1J499RBTDF")
      (footprint "FP-RP73P-1J-MFG")
      (description "RP73P 0603 499Ω 0.166W 25ppm/°C 0.10% 100V")
      (fields (field (name "RESISTANCE") "499Ω") (field (name "TOLERANCE") "0.001"))
      (libsource (lib "Altium Content Vault") (part "1029c3af85768c4190bb7ad29bc67b5"))
    )
    (comp (ref "R_VSPIKE")
      (value "RP73PF1J499RBTDF")
      (footprint "FP-RP73P-1J-MFG")
      (description "RP73P 0603 499Ω 0.166W 25ppm/°C 0.10% 100V")
      (fields (field (name "RESISTANCE") "499Ω") (field (name "TOLERANCE") "0.001"))
      (libsource (lib "Altium Content Vault") (part "1029c3af85768c4190bb7ad29bc67b5"))
    )
    (comp (ref "R_VSS_SYN")
      (value "RP73PF1J499RBTDF")
      (footprint "FP-RP73P-1J-MFG")
      (description "RP73P 0603 499Ω 0.166W 25ppm/°C 0.10% 100V")
      (fields (field (name "RESISTANCE") "499Ω") (field (name "TOLERANCE") "0.001"))
      (libsource (lib "Altium Content Vault") (part "1029c3af85768c4190bb7ad29bc67b5"))
    )
    (comp (ref "R_VTAU0")
      (value "1M")
      (footprint "FP-CRCW0603-e3-MFG")
      (description "RES Thick Film, 1MΩ, 1%, 0.1W, 100ppm/°C, 0603")
      (fields (field (name "TOLERANCE") "1%"))
      (libsource (lib "Altium Content Vault") (part "1029c3af85768c4190bb7ad29bc67b5"))
    )
    (comp (ref "R_VTAU1")
      (value "1M")
      (footprint "FP-CRCW0603-e3-MFG")
      (description "RES Thick Film, 1MΩ, 1%, 0.1W, 100ppm/°C, 0603")
      (fields (field (name "TOLERANCE") "1%"))
      (libsource (lib "Altium Content Vault") (part "1029c3af85768c4190bb7ad29bc67b5"))
    )
    (comp (ref "R_VTAU2")
      (value "1M")
      (footprint "FP-CRCW0603-e3-MFG")
      (description "RES Thick Film, 1MΩ, 1%, 0.1W, 100ppm/°C, 0603")
      (fields (field (name "TOLERANCE") "1%"))
      (libsource (lib "Altium Content Vault") (part "1029c3af85768c4190bb7ad29bc67b5"))
    )
    (comp (ref "R_VTAU3")
      (value "1M")
      (footprint "FP-CRCW0603-e3-MFG")
      (description "RES Thick Film, 1MΩ, 1%, 0.1W, 100ppm/°C, 0603")
      (fields (field (name "TOLERANCE") "1%"))
      (libsource (lib "Altium Content Vault") (part "1029c3af85768c4190bb7ad29bc67b5"))
    )
    (comp (ref "R_VTHRESH")
      (value "RP73PF1J499RBTDF")
      (footprint "FP-RP73P-1J-MFG")
      (description "RP73P 0603 499Ω 0.166W 25ppm/°C 0.10% 100V")
      (fields (field (name "RESISTANCE") "499Ω") (field (name "TOLERANCE") "0.001"))
      (libsource (lib "Altium Content Vault") (part "1029c3af85768c4190bb7ad29bc67b5"))
    )
    (comp (ref "R_VWIDTH_HI")
      (value "RN731ETTP50R0F50")
      (footprint "FP-RN731E-IPC_A")
      (description "50Ω ±1% 0.063W, 1/16W Chip Resistor 0402 (1005 Metric) Moisture Resistant Thin Film")
      (fields (field (name "RESISTANCE") "50"))
      (libsource (lib "Altium Content Vault") (part "1029c3af85768c4190bb7ad29bc67b5"))
    )
    (comp (ref "R_VWIDTH_LO")
      (value "RN731ETTP50R0F50")
      (footprint "FP-RN731E-IPC_A")
      (description "50Ω ±1% 0.063W, 1/16W Chip Resistor 0402 (1005 Metric) Moisture Resistant Thin Film")
      (fields (field (name "RESISTANCE") "50"))
      (libsource (lib "Altium Content Vault") (part "1029c3af85768c4190bb7ad29bc67b5"))
    )
    (comp (ref "R_WIDTH_BIAS")
      (value "1M")
      (footprint "FP-CRCW0603-e3-MFG")
      (description "RES Thick Film, 1MΩ, 1%, 0.1W, 100ppm/°C, 0603")
      (fields (field (name "TOLERANCE") "1%"))
      (libsource (lib "Altium Content Vault") (part "1029c3af85768c4190bb7ad29bc67b5"))
    )
  )
  (nets
    (net (code "1") (name "/+VDC") (class "Default")
      (node (ref "H_PWR_5V") (pin "1") (pinfunction "1_1") (pintype "passive"))
    )
    (net (code "2") (name "/+VDC_1.8") (class "Default")
      (node (ref "H_PWR_1.8V") (pin "1") (pinfunction "1_1") (pintype "passive"))
    )
    (net (code "3") (name "/+VDC_1.8_LDO") (class "Default")
      (node (ref "H_PWR_1.8V") (pin "2") (pinfunction "2_2") (pintype "passive"))
    )
    (net (code "4") (name "/+VDC_3.3") (class "Default")
      (node (ref "H_PWR_3.3V") (pin "1") (pinfunction "1_1") (pintype "passive"))
      (node (ref "H_VDD_3.3") (pin "1") (pinfunction "1_1") (pintype "passive"))
    )
    (net (code "5") (name "/+VDC_3.3_LDO") (class "Default")
      (node (ref "H_PWR_3.3V") (pin "2") (pinfunction "2_2") (pintype "passive"))
    )
    (net (code "6") (name "/+VDC_LDO") (class "Default")
      (node (ref "H_PWR_5V") (pin "2") (pinfunction "2_2") (pintype "passive"))
    )
    (net (code "7") (name "/AVDD") (class "Default")
      (node (ref "C_GCOMP") (pin "1") (pinfunction "1_1") (pintype "passive"))
      (node (ref "C_VAMP_HIGH") (pin "1") (pinfunction "1_1") (pintype "passive"))
      (node (ref "C_VBIAS") (pin "1") (pinfunction "1_1") (pintype "passive"))
      (node (ref "C_VBP") (pin "1") (pinfunction "1_1") (pintype "passive"))
      (node (ref "C_VIN_IBIAS") (pin "1") (pinfunction "1_1") (pintype "passive"))
      (node (ref "C_VSPIKE") (pin "1") (pinfunction "1_1") (pintype "passive"))
      (node (ref "C_VWIDTH_HI") (pin "1") (pinfunction "1_1") (pintype "passive"))
      (node (ref "C_VpupReq") (pin "1") (pinfunction "1_1") (pintype "passive"))
      (node (ref "C_Vpup_arb") (pin "1") (pinfunction "1_1") (pintype "passive"))
      (node (ref "H_AVDD") (pin "2") (pinfunction "2_2") (pintype "passive"))
    )
    (net (code "8") (name "/AVDD_DAC") (class "Default")
      (node (ref "H_AVDD") (pin "1") (pinfunction "1_1") (pintype "passive"))
    )
    (net (code "9") (name "/AVDD_LDO") (class "Default")
      (node (ref "H_AVDD") (pin "3") (pinfunction "3_3") (pintype "passive"))
    )
    (net (code "31") (name "/DVDD") (class "Default")
      (node (ref "H_DVDD") (pin "2") (pinfunction "2_2") (pintype "passive"))
    )
    (net (code "32") (name "/DVDD_DAC") (class "Default")
      (node (ref "H_DVDD") (pin "1") (pinfunction "1_1") (pintype "passive"))
    )
    (net (code "33") (name "/DVDD_HIGH") (class "Default")
      (node (ref "H_DVDD_HIGH") (pin "2") (pinfunction "2_2") (pintype "passive"))
    )
    (net (code "34") (name "/DVDD_HIGH_DAC") (class "Default")
      (node (ref "H_DVDD_HIGH") (pin "1") (pinfunction "1_1") (pintype "passive"))
    )
    (net (code "35") (name "/DVDD_HIGH_LDO") (class "Default")
      (node (ref "H_DVDD_HIGH") (pin "3") (pinfunction "3_3") (pintype "passive"))
    )
    (net (code "36") (name "/DVDD_LDO") (class "Default")
      (node (ref "H_DVDD") (pin "3") (pinfunction "3_3") (pintype "passive"))
    )
    (net (code "37") (name "/ELEAK") (class "Default")
      (node (ref "C_ELEAK") (pin "2") (pinfunction "2_2") (pintype "passive"))
      (node (ref "H_ELEAK") (pin "2") (pinfunction "2_2") (pintype "passive"))
      (node (ref "R_ELEAK") (pin "2") (pinfunction "2_2") (pintype "passive"))
    )
    (net (code "38") (name "/ELEAK_DAC") (class "Default")
      (node (ref "H_ELEAK") (pin "1") (pinfunction "1_1") (pintype "passive"))
      (node (ref "R_ELEAK") (pin "1") (pinfunction "1_1") (pintype "passive"))
    )
    (net (code "39") (name "/EVDD") (class "Default")
      (node (ref "H_EVDD") (pin "2") (pinfunction "2_2") (pintype "passive"))
    )
    (net (code "40") (name "/EVDD_DAC") (class "Default")
      (node (ref "H_EVDD") (pin "1") (pinfunction "1_1") (pintype "passive"))
    )
    (net (code "41") (name "/EVDD_LDO") (class "Default")
      (node (ref "H_EVDD") (pin "3") (pinfunction "3_3") (pintype "passive"))
    )
    (net (code "42") (name "/E_REV0") (class "Default")
      (node (ref "C_EREV0") (pin "2") (pinfunction "2_2") (pintype "passive"))
      (node (ref "H_EREV0") (pin "2") (pinfunction "2_2") (pintype "passive"))
      (node (ref "R_EREV0") (pin "2") (pinfunction "2_2") (pintype "passive"))
    )
    (net (code "43") (name "/E_REV1") (class "Default")
      (node (ref "C_EREV1") (pin "2") (pinfunction "2_2") (pintype "passive"))
      (node (ref "H_EREV1") (pin "2") (pinfunction "2_2") (pintype "passive"))
      (node (ref "R_EREV1") (pin "2") (pinfunction "2_2") (pintype "passive"))
    )
    (net (code "44") (name "/E_REV2") (class "Default")
      (node (ref "C_EREV2") (pin "2") (pinfunction "2_2") (pintype "passive"))
      (node (ref "H_EREV2") (pin "2") (pinfunction "2_2") (pintype "passive"))
      (node (ref "R_EREV2") (pin "2") (pinfunction "2_2") (pintype "passive"))
    )
    (net (code "45") (name "/E_REV3") (class "Default")
      (node (ref "C_EREV3") (pin "2") (pinfunction "2_2") (pintype "passive"))
      (node (ref "H_EREV3") (pin "2") (pinfunction "2_2") (pintype "passive"))
      (node (ref "R_EREV3") (pin "2") (pinfunction "2_2") (pintype "passive"))
    )
    (net (code "47") (name "/GCOMP") (class "Default")
      (node (ref "C_GCOMP") (pin "2") (pinfunction "2_2") (pintype "passive"))
      (node (ref "H_GCOMP") (pin "2") (pinfunction "2_2") (pintype "passive"))
      (node (ref "R_COMP") (pin "1") (pinfunction "1_1") (pintype "passive"))
    )
    (net (code "48") (name "/GCOMP_DAC") (class "Default")
      (node (ref "H_GCOMP") (pin "1") (pinfunction "1_1") (pintype "passive"))
      (node (ref "R_COMP") (pin "2") (pinfunction "2_2") (pintype "passive"))
    )
    (net (code "49") (name "/GLEAK_DISTAL") (class "Default")
      (node (ref "C_GLEAKD") (pin "2") (pinfunction "2_2") (pintype "passive"))
      (node (ref "H_GLEAKD") (pin "2") (pinfunction "2_2") (pintype "passive"))
      (node (ref "R_GLEAKD") (pin "1") (pinfunction "1_1") (pintype "passive"))
    )
    (net (code "50") (name "/GLEAK_DISTAL_DAC") (class "Default")
      (node (ref "H_GLEAKD") (pin "1") (pinfunction "1_1") (pintype "passive"))
      (node (ref "R_GLEAKD") (pin "2") (pinfunction "2_2") (pintype "passive"))
    )
    (net (code "51") (name "/GLEAK_PROXIMAL") (class "Default")
      (node (ref "C_GLEAKP") (pin "2") (pinfunction "2_2") (pintype "passive"))
      (node (ref "H_GLEAKP") (pin "2") (pinfunction "2_2") (pintype "passive"))
      (node (ref "R_GLEAKP") (pin "1") (pinfunction "1_1") (pintype "passive"))
    )
    (net (code "52") (name "/GLEAK_PROXIMAL_DAC") (class "Default")
      (node (ref "H_GLEAKP") (pin "1") (pinfunction "1_1") (pintype "passive"))
      (node (ref "R_GLEAKP") (pin "2") (pinfunction "2_2") (pintype "passive"))
    )
    (net (code "53") (name "/GND") (class "Default")
      (node (ref "C_ELEAK") (pin "1") (pinfunction "1_1") (pintype "passive"))
      (node (ref "C_EREV0") (pin "1") (pinfunction "1_1") (pintype "passive"))
      (node (ref "C_EREV1") (pin "1") (pinfunction "1_1") (pintype "passive"))
      (node (ref "C_EREV2") (pin "1") (pinfunction "1_1") (pintype "passive"))
      (node (ref "C_EREV3") (pin "1") (pinfunction "1_1") (pintype "passive"))
      (node (ref "C_GLEAKD") (pin "1") (pinfunction "1_1") (pintype "passive"))
      (node (ref "C_GLEAKP") (pin "1") (pinfunction "1_1") (pintype "passive"))
      (node (ref "C_SYN_DRIVELO") (pin "1") (pinfunction "1_1") (pintype "passive"))
      (node (ref "C_VAMP_LOW") (pin "1") (pinfunction "1_1") (pintype "passive"))
      (node (ref "C_VBIAS_BUFF") (pin "1") (pinfunction "1_1") (pintype "passive"))
      (node (ref "C_VBIAS_SF") (pin "1") (pinfunction "1_1") (pintype "passive"))
      (node (ref "C_VPDN") (pin "1") (pinfunction "1_1") (pintype "passive"))
      (node (ref "C_VREFR") (pin "1") (pinfunction "1_1") (pintype "passive"))
      (node (ref "C_VRESET") (pin "1") (pinfunction "1_1") (pintype "passive"))
      (node (ref "C_VSS_SYN") (pin "1") (pinfunction "1_1") (pintype "passive"))
      (node (ref "C_VTAU0") (pin "1") (pinfunction "1_1") (pintype "passive"))
      (node (ref "C_VTAU1") (pin "1") (pinfunction "1_1") (pintype "passive"))
      (node (ref "C_VTAU2") (pin "1") (pinfunction "1_1") (pintype "passive"))
      (node (ref "C_VTAU3") (pin "1") (pinfunction "1_1") (pintype "passive"))
      (node (ref "C_VTHRESH") (pin "1") (pinfunction "1_1") (pintype "passive"))
      (node (ref "C_VWIDTH_LO") (pin "1") (pinfunction "1_1") (pintype "passive"))
      (node (ref "C_WIDTH_BIAS") (pin "1") (pinfunction "1_1") (pintype "passive"))
    )
    (net (code "54") (name "/SYNAPSE_DRIVE_LOW") (class "Default")
      (node (ref "C_SYN_DRIVELO") (pin "2") (pinfunction "2_2") (pintype "passive"))
      (node (ref "H_SYN_DRIVELO") (pin "2") (pinfunction "2_2") (pintype "passive"))
      (node (ref "R_SYN_DRIVELO") (pin "2") (pinfunction "2_2") (pintype "passive"))
    )
    (net (code "55") (name "/SYNAPSE_DRIVE_LOW_DAC") (class "Default")
      (node (ref "H_SYN_DRIVELO") (pin "1") (pinfunction "1_1") (pintype "passive"))
      (node (ref "R_SYN_DRIVELO") (pin "1") (pinfunction "1_1") (pintype "passive"))
    )
    (net (code "56") (name "/VAMP_HIGH") (class "Default")
      (node (ref "C_VAMP_HIGH") (pin "2") (pinfunction "2_2") (pintype "passive"))
      (node (ref "H_VAMP_HIGH") (pin "2") (pinfunction "2_2") (pintype "passive"))
      (node (ref "R_VAMP_HIGH") (pin "2") (pinfunction "2_2") (pintype "passive"))
    )
    (net (code "57") (name "/VAMP_HIGH_DAC") (class "Default")
      (node (ref "H_VAMP_HIGH") (pin "1") (pinfunction "1_1") (pintype "passive"))
      (node (ref "R_VAMP_HIGH") (pin "1") (pinfunction "1_1") (pintype "passive"))
    )
    (net (code "58") (name "/VAMP_LOW") (class "Default")
      (node (ref "C_VAMP_LOW") (pin "2") (pinfunction "2_2") (pintype "passive"))
      (node (ref "H_VAMP_LOW") (pin "2") (pinfunction "2_2") (pintype "passive"))
      (node (ref "R_VAMP_LOW") (pin "2") (pinfunction "2_2") (pintype "passive"))
    )
    (net (code "59") (name "/VAMP_LOW_DAC") (class "Default")
      (node (ref "H_VAMP_LOW") (pin "1") (pinfunction "1_1") (pintype "passive"))
      (node (ref "R_VAMP_LOW") (pin "1") (pinfunction "1_1") (pintype "passive"))
    )
    (net (code "60") (name "/VBIAS") (class "Default")
      (node (ref "C_VBIAS") (pin "2") (pinfunction "2_2") (pintype "passive"))
      (node (ref "H_VBIAS") (pin "2") (pinfunction "2_2") (pintype "passive"))
      (node (ref "R_VBIAS") (pin "1") (pinfunction "1_1") (pintype "passive"))
    )
    (net (code "61") (name "/VBIAS_DAC") (class "Default")
      (node (ref "H_VBIAS") (pin "1") (pinfunction "1_1") (pintype "passive"))
      (node (ref "R_VBIAS") (pin "2") (pinfunction "2_2") (pintype "passive"))
    )
    (net (code "62") (name "/VBIAS_SF") (class "Default")
      (node (ref "C_VBIAS_SF") (pin "2") (pinfunction "2_2") (pintype "passive"))
      (node (ref "H_VBIAS_SF") (pin "2") (pinfunction "2_2") (pintype "passive"))
      (node (ref "R_VBIAS_SF") (pin "1") (pinfunction "1_1") (pintype "passive"))
    )
    (net (code "63") (name "/VBIAS_SF_DAC") (class "Default")
      (node (ref "H_VBIAS_SF") (pin "1") (pinfunction "1_1") (pintype "passive"))
      (node (ref "R_VBIAS_SF") (pin "2") (pinfunction "2_2") (pintype "passive"))
    )
    (net (code "64") (name "/VBIAS_UNITYBUFFER") (class "Default")
      (node (ref "C_VBIAS_BUFF") (pin "2") (pinfunction "2_2") (pintype "passive"))
      (node (ref "H_VBIAS_BUFF") (pin "2") (pinfunction "2_2") (pintype "passive"))
      (node (ref "R_VBIAS_BUFF") (pin "1") (pinfunction "1_1") (pintype "passive"))
    )
    (net (code "65") (name "/VBIAS_UNITYBUFFER_DAC") (class "Default")
      (node (ref "H_VBIAS_BUFF") (pin "1") (pinfunction "1_1") (pintype "passive"))
      (node (ref "R_VBIAS_BUFF") (pin "2") (pinfunction "2_2") (pintype "passive"))
    )
    (net (code "66") (name "/VBP") (class "Default")
      (node (ref "C_VBP") (pin "2") (pinfunction "2_2") (pintype "passive"))
      (node (ref "H_VBP") (pin "2") (pinfunction "2_2") (pintype "passive"))
      (node (ref "R_VBP") (pin "1") (pinfunction "1_1") (pintype "passive"))
    )
    (net (code "67") (name "/VBP_DAC") (class "Default")
      (node (ref "H_VBP") (pin "1") (pinfunction "1_1") (pintype "passive"))
      (node (ref "R_VBP") (pin "2") (pinfunction "2_2") (pintype "passive"))
    )
    (net (code "68") (name "/VDD_1.2") (class "Default")
      (node (ref "H_VDD_1.2") (pin "2") (pinfunction "2_2") (pintype "passive"))
    )
    (net (code "69") (name "/VDD_1.2_DAC") (class "Default")
      (node (ref "H_VDD_1.2") (pin "1") (pinfunction "1_1") (pintype "passive"))
    )
    (net (code "70") (name "/VDD_1.2_LDO") (class "Default")
      (node (ref "H_VDD_1.2") (pin "3") (pinfunction "3_3") (pintype "passive"))
    )
    (net (code "71") (name "/VDD_3.3") (class "Default")
      (node (ref "H_VDD_3.3") (pin "2") (pinfunction "2_2") (pintype "passive"))
    )
    (net (code "72") (name "/VDD_3.3_LDO") (class "Default")
      (node (ref "H_VDD_3.3") (pin "3") (pinfunction "3_3") (pintype "passive"))
    )
    (net (code "73") (name "/VINPUT_CURRENT_BIAS") (class "Default")
      (node (ref "C_VIN_IBIAS") (pin "2") (pinfunction "2_2") (pintype "passive"))
      (node (ref "H_VIN_IBIAS") (pin "2") (pinfunction "2_2") (pintype "passive"))
      (node (ref "R_VIN_IBIAS") (pin "1") (pinfunction "1_1") (pintype "passive"))
    )
    (net (code "74") (name "/VINPUT_CURRENT_BIAS_DAC") (class "Default")
      (node (ref "H_VIN_IBIAS") (pin "1") (pinfunction "1_1") (pintype "passive"))
      (node (ref "R_VIN_IBIAS") (pin "2") (pinfunction "2_2") (pintype "passive"))
    )
    (net (code "75") (name "/VPDN") (class "Default")
      (node (ref "C_VPDN") (pin "2") (pinfunction "2_2") (pintype "passive"))
      (node (ref "H_VPDN") (pin "2") (pinfunction "2_2") (pintype "passive"))
      (node (ref "R_VPDN") (pin "1") (pinfunction "1_1") (pintype "passive"))
    )
    (net (code "76") (name "/VPDN_DAC") (class "Default")
      (node (ref "H_VPDN") (pin "1") (pinfunction "1_1") (pintype "passive"))
      (node (ref "R_VPDN") (pin "2") (pinfunction "2_2") (pintype "passive"))
    )
    (net (code "77") (name "/VREFR") (class "Default")
      (node (ref "C_VREFR") (pin "2") (pinfunction "2_2") (pintype "passive"))
      (node (ref "H_VEFR") (pin "2") (pinfunction "2_2") (pintype "passive"))
      (node (ref "R_VREFR") (pin "1") (pinfunction "1_1") (pintype "passive"))
    )
    (net (code "78") (name "/VREFR_DAC") (class "Default")
      (node (ref "H_VEFR") (pin "1") (pinfunction "1_1") (pintype "passive"))
      (node (ref "R_VREFR") (pin "2") (pinfunction "2_2") (pintype "passive"))
    )
    (net (code "79") (name "/VREF_1.8") (class "Default")
      (node (ref "H_VREF_1.8") (pin "2") (pinfunction "2_2") (pintype "passive"))
    )
    (net (code "80") (name "/VREF_1.8_DAC") (class "Default")
      (node (ref "H_VREF_1.8") (pin "1") (pinfunction "1_1") (pintype "passive"))
    )
    (net (code "81") (name "/VREF_1.8_LDO") (class "Default")
      (node (ref "H_VREF_1.8") (pin "3") (pinfunction "3_3") (pintype "passive"))
    )
    (net (code "82") (name "/VREF_2") (class "Default")
      (node (ref "H_VREF_2") (pin "2") (pinfunction "2_2") (pintype "passive"))
    )
    (net (code "83") (name "/VREF_2_DAC") (class "Default")
      (node (ref "H_VREF_2") (pin "1") (pinfunction "1_1") (pintype "passive"))
    )
    (net (code "84") (name "/VREF_2_LDO") (class "Default")
      (node (ref "H_VREF_2") (pin "3") (pinfunction "3_3") (pintype "passive"))
    )
    (net (code "85") (name "/VRESET") (class "Default")
      (node (ref "C_VRESET") (pin "2") (pinfunction "2_2") (pintype "passive"))
      (node (ref "H_VRESET") (pin "2") (pinfunction "2_2") (pintype "passive"))
      (node (ref "R_VRESET") (pin "2") (pinfunction "2_2") (pintype "passive"))
    )
    (net (code "86") (name "/VRESET_DAC") (class "Default")
      (node (ref "H_VRESET") (pin "1") (pinfunction "1_1") (pintype "passive"))
      (node (ref "R_VRESET") (pin "1") (pinfunction "1_1") (pintype "passive"))
    )
    (net (code "87") (name "/VSPIKE") (class "Default")
      (node (ref "C_VSPIKE") (pin "2") (pinfunction "2_2") (pintype "passive"))
      (node (ref "H_VSPIKE") (pin "2") (pinfunction "2_2") (pintype "passive"))
      (node (ref "R_VSPIKE") (pin "2") (pinfunction "2_2") (pintype "passive"))
    )
    (net (code "88") (name "/VSPIKE_DAC") (class "Default")
      (node (ref "H_VSPIKE") (pin "1") (pinfunction "1_1") (pintype "passive"))
      (node (ref "R_VSPIKE") (pin "1") (pinfunction "1_1") (pintype "passive"))
    )
    (net (code "89") (name "/VSS_SYNAPSE") (class "Default")
      (node (ref "C_VSS_SYN") (pin "2") (pinfunction "2_2") (pintype "passive"))
      (node (ref "H_VSS_SYN") (pin "2") (pinfunction "2_2") (pintype "passive"))
      (node (ref "R_VSS_SYN") (pin "2") (pinfunction "2_2") (pintype "passive"))
    )
    (net (code "90") (name "/VSS_SYN_DAC") (class "Default")
      (node (ref "H_VSS_SYN") (pin "1") (pinfunction "1_1") (pintype "passive"))
      (node (ref "R_VSS_SYN") (pin "1") (pinfunction "1_1") (pintype "passive"))
    )
    (net (code "91") (name "/VTHRESH") (class "Default")
      (node (ref "C_VTHRESH") (pin "2") (pinfunction "2_2") (pintype "passive"))
      (node (ref "H_VTHRESH") (pin "2") (pinfunction "2_2") (pintype "passive"))
      (node (ref "R_VTHRESH") (pin "2") (pinfunction "2_2") (pintype "passive"))
    )
    (net (code "92") (name "/VTHRESH_DAC") (class "Default")
      (node (ref "H_VTHRESH") (pin "1") (pinfunction "1_1") (pintype "passive"))
      (node (ref "R_VTHRESH") (pin "1") (pinfunction "1_1") (pintype "passive"))
    )
    (net (code "93") (name "/V_EREV0_DAC") (class "Default")
      (node (ref "H_EREV0") (pin "1") (pinfunction "1_1") (pintype "passive"))
      (node (ref "R_EREV0") (pin "1") (pinfunction "1_1") (pintype "passive"))
    )
    (net (code "94") (name "/V_EREV1_DAC") (class "Default")
      (node (ref "H_EREV1") (pin "1") (pinfunction "1_1") (pintype "passive"))
      (node (ref "R_EREV1") (pin "1") (pinfunction "1_1") (pintype "passive"))
    )
    (net (code "95") (name "/V_EREV2_DAC") (class "Default")
      (node (ref "H_EREV2") (pin "1") (pinfunction "1_1") (pintype "passive"))
      (node (ref "R_EREV2") (pin "1") (pinfunction "1_1") (pintype "passive"))
    )
    (net (code "96") (name "/V_EREV3_DAC") (class "Default")
      (node (ref "H_EREV3") (pin "1") (pinfunction "1_1") (pintype "passive"))
      (node (ref "R_EREV3") (pin "1") (pinfunction "1_1") (pintype "passive"))
    )
    (net (code "97") (name "/V_TAU0") (class "Default")
      (node (ref "C_VTAU0") (pin "2") (pinfunction "2_2") (pintype "passive"))
      (node (ref "H_VTAU0") (pin "2") (pinfunction "2_2") (pintype "passive"))
      (node (ref "R_VTAU0") (pin "1") (pinfunction "1_1") (pintype "passive"))
    )
    (net (code "98") (name "/V_TAU0_DAC") (class "Default")
      (node (ref "H_VTAU0") (pin "1") (pinfunction "1_1") (pintype "passive"))
      (node (ref "R_VTAU0") (pin "2") (pinfunction "2_2") (pintype "passive"))
    )
    (net (code "99") (name "/V_TAU1") (class "Default")
      (node (ref "C_VTAU1") (pin "2") (pinfunction "2_2") (pintype "passive"))
      (node (ref "H_VTAU1") (pin "2") (pinfunction "2_2") (pintype "passive"))
      (node (ref "R_VTAU1") (pin "1") (pinfunction "1_1") (pintype "passive"))
    )
    (net (code "100") (name "/V_TAU1_DAC") (class "Default")
      (node (ref "H_VTAU1") (pin "1") (pinfunction "1_1") (pintype "passive"))
      (node (ref "R_VTAU1") (pin "2") (pinfunction "2_2") (pintype "passive"))
    )
    (net (code "101") (name "/V_TAU2") (class "Default")
      (node (ref "C_VTAU2") (pin "2") (pinfunction "2_2") (pintype "passive"))
      (node (ref "H_VTAU2") (pin "2") (pinfunction "2_2") (pintype "passive"))
      (node (ref "R_VTAU2") (pin "1") (pinfunction "1_1") (pintype "passive"))
    )
    (net (code "102") (name "/V_TAU2_DAC") (class "Default")
      (node (ref "H_VTAU2") (pin "1") (pinfunction "1_1") (pintype "passive"))
      (node (ref "R_VTAU2") (pin "2") (pinfunction "2_2") (pintype "passive"))
    )
    (net (code "103") (name "/V_TAU3") (class "Default")
      (node (ref "C_VTAU3") (pin "2") (pinfunction "2_2") (pintype "passive"))
      (node (ref "H_VTAU3") (pin "2") (pinfunction "2_2") (pintype "passive"))
      (node (ref "R_VTAU3") (pin "1") (pinfunction "1_1") (pintype "passive"))
    )
    (net (code "104") (name "/V_TAU3_DAC") (class "Default")
      (node (ref "H_VTAU3") (pin "1") (pinfunction "1_1") (pintype "passive"))
      (node (ref "R_VTAU3") (pin "2") (pinfunction "2_2") (pintype "passive"))
    )
    (net (code "106") (name "/VpupReq") (class "Default")
      (node (ref "C_VpupReq") (pin "2") (pinfunction "2_2") (pintype "passive"))
      (node (ref "H_VpupReq") (pin "2") (pinfunction "2_2") (pintype "passive"))
      (node (ref "R_VpupReq") (pin "1") (pinfunction "1_1") (pintype "passive"))
    )
    (net (code "107") (name "/VpupReq_DAC") (class "Default")
      (node (ref "H_VpupReq") (pin "1") (pinfunction "1_1") (pintype "passive"))
      (node (ref "R_VpupReq") (pin "2") (pinfunction "2_2") (pintype "passive"))
    )
    (net (code "108") (name "/Vpup_arb") (class "Default")
      (node (ref "C_Vpup_arb") (pin "2") (pinfunction "2_2") (pintype "passive"))
      (node (ref "H_Vpup_arb") (pin "2") (pinfunction "2_2") (pintype "passive"))
      (node (ref "R_Vpup_arb") (pin "1") (pinfunction "1_1") (pintype "passive"))
    )
    (net (code "109") (name "/Vpup_arb_DAC") (class "Default")
      (node (ref "H_Vpup_arb") (pin "1") (pinfunction "1_1") (pintype "passive"))
      (node (ref "R_Vpup_arb") (pin "2") (pinfunction "2_2") (pintype "passive"))
    )
    (net (code "110") (name "/WIDTH_BIAS") (class "Default")
      (node (ref "C_WIDTH_BIAS") (pin "2") (pinfunction "2_2") (pintype "passive"))
      (node (ref "H_WIDTH_BIAS") (pin "2") (pinfunction "2_2") (pintype "passive"))
      (node (ref "R_WIDTH_BIAS") (pin "1") (pinfunction "1_1") (pintype "passive"))
    )
    (net (code "111") (name "/WIDTH_BIAS_DAC") (class "Default")
      (node (ref "H_WIDTH_BIAS") (pin "1") (pinfunction "1_1") (pintype "passive"))
      (node (ref "R_WIDTH_BIAS") (pin "2") (pinfunction "2_2") (pintype "passive"))
    )
    (net (code "112") (name "/WIDTH_BIAS_HIGH") (class "Default")
      (node (ref "C_VWIDTH_HI") (pin "2") (pinfunction "2_2") (pintype "passive"))
      (node (ref "H_VWIDTH_HI") (pin "2") (pinfunction "2_2") (pintype "passive"))
      (node (ref "R_VWIDTH_HI") (pin "2") (pinfunction "2_2") (pintype "passive"))
    )
    (net (code "113") (name "/WIDTH_BIAS_HIGH_DAC") (class "Default")
      (node (ref "H_VWIDTH_HI") (pin "1") (pinfunction "1_1") (pintype "passive"))
      (node (ref "R_VWIDTH_HI") (pin "1") (pinfunction "1_1") (pintype "passive"))
    )
    (net (code "114") (name "/WIDTH_BIAS_LOW") (class "Default")
      (node (ref "C_VWIDTH_LO") (pin "2") (pinfunction "2_2") (pintype "passive"))
      (node (ref "H_VWIDTH_LO") (pin "2") (pinfunction "2_2") (pintype "passive"))
      (node (ref "R_VWIDTH_LO") (pin "2") (pinfunction "2_2") (pintype "passive"))
    )
    (net (code "115") (name "/WIDTH_BIAS_LOW_DAC") (class "Default")
      (node (ref "H_VWIDTH_LO") (pin "1") (pinfunction "1_1") (pintype "passive"))
      (node (ref "R_VWIDTH_LO") (pin "1") (pinfunction "1_1") (pintype "passive"))
    )
  )
)
